# current_sense.net
KiCad netlist of a schematic drawn in Altium Designer
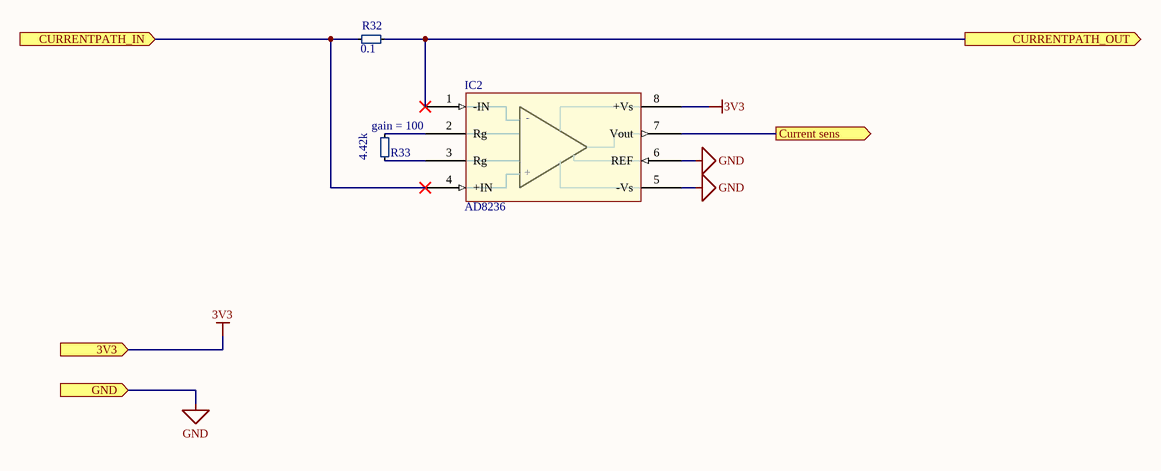
[diagram p0: current_sense.SchDoc]

(export (version "E")
  (design (tool "Eeschema 10.0.6"))
  (components
    (comp (ref "IC2")
      (value "AD8236")
      (footprint "8-MSOP")
      (description "IC OPAMP INSTR 23KHZ RRO 8MSOP")
      (libsource (lib "concord server") (part "AD8236"))
    )
    (comp (ref "R32")
      (value "ERJ-8BSFR10V")
      (footprint "Chip2PinSM127P600-8N")
      (fields (field (name "RESISTANCE") "0.1") (field (name "TOLERANCE") "1%"))
      (libsource (lib "concord server") (part "resistor_european"))
    )
    (comp (ref "R33")
      (value "RC0402FR-074K42L")
      (footprint "SMD_0402(1005)_M")
      (description "RES SMD 4.42K OHM 1% 1/16W 0402")
      (fields (field (name "RESISTANCE") "4.42k") (field (name "TOLERANCE") "1%"))
      (libsource (lib "concord server") (part "resistor_european"))
    )
  )
  (nets
    (net (code "1") (name "/CURRENTPATH_IN") (class "Default")
      (node (ref "IC2") (pin "4") (pinfunction "+IN_4") (pintype "input"))
      (node (ref "R32") (pin "1") (pinfunction "1_1") (pintype "passive"))
    )
    (net (code "2") (name "/CURRENTPATH_OUT") (class "Default")
      (node (ref "IC2") (pin "1") (pinfunction "-IN_1") (pintype "input"))
      (node (ref "R32") (pin "2") (pinfunction "2_2") (pintype "passive"))
    )
    (net (code "3") (name "/Current sens") (class "Default")
      (node (ref "IC2") (pin "7") (pinfunction "Vout_7") (pintype "output"))
    )
    (net (code "4") (name "3V3") (class "Default")
      (node (ref "IC2") (pin "8") (pinfunction "+Vs_8") (pintype "power_in"))
    )
    (net (code "5") (name "GND") (class "Default")
      (node (ref "IC2") (pin "5") (pinfunction "-Vs_5") (pintype "power_in"))
      (node (ref "IC2") (pin "6") (pinfunction "REF_6") (pintype "input"))
    )
    (net (code "6") (name "Net-(IC2-Rg-Pad2)") (class "Default")
      (node (ref "IC2") (pin "2") (pinfunction "Rg_2") (pintype "passive"))
      (node (ref "R33") (pin "2") (pinfunction "2_2") (pintype "passive"))
    )
    (net (code "7") (name "Net-(IC2-Rg-Pad3)") (class "Default")
      (node (ref "IC2") (pin "3") (pinfunction "Rg_3") (pintype "passive"))
      (node (ref "R33") (pin "1") (pinfunction "1_1") (pintype "passive"))
    )
  )
)
